# simaservo.net
KiCad netlist of a schematic drawn in EAGLE
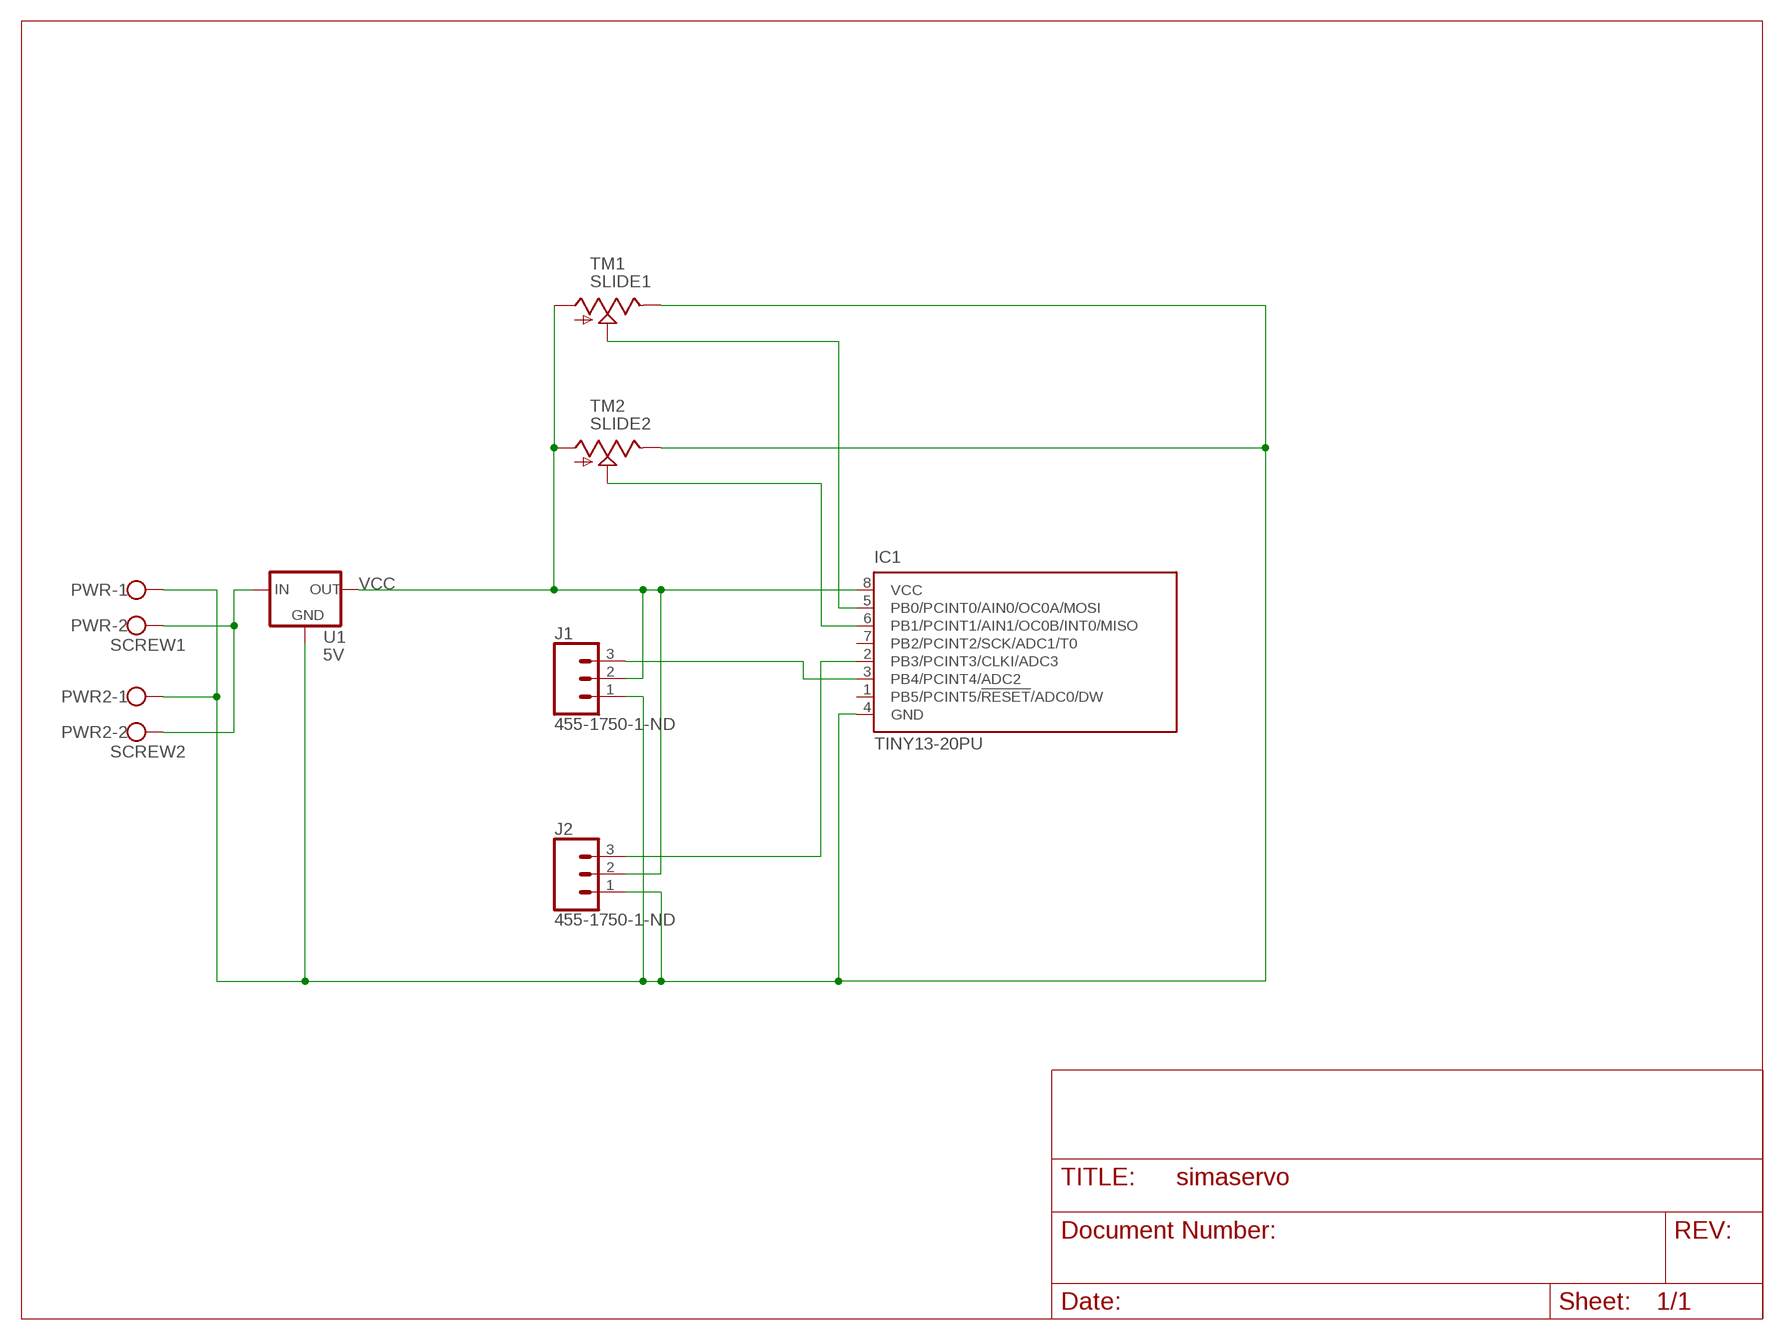
[diagram p0: schematic, sheet 1]

(export (version "E")
  (design (tool "Eeschema 10.0.6"))
  (components
    (comp (ref "IC1")
      (value "TINY13-20PU")
      (footprint "eagle-import:DIL08")
      (fields (field (name "MPN") "ATTINY13-20PU"))
      (libsource (lib "eagle-import") (part "TINY13PU-20"))
    )
    (comp (ref "J1")
      (value "455-1750-1-ND")
      (footprint "eagle-import:1X03")
      (libsource (lib "eagle-import") (part "CONN_03"))
    )
    (comp (ref "J2")
      (value "455-1750-1-ND")
      (footprint "eagle-import:1X03")
      (libsource (lib "eagle-import") (part "CONN_03"))
    )
    (comp (ref "PWR")
      (value "SCREW1")
      (footprint "eagle-import:W237-102")
      (fields (field (name "MPN") "237-102"))
      (libsource (lib "eagle-import") (part "W237-102"))
    )
    (comp (ref "PWR2")
      (value "SCREW2")
      (footprint "eagle-import:W237-102")
      (fields (field (name "MPN") "237-102"))
      (libsource (lib "eagle-import") (part "W237-102"))
    )
    (comp (ref "TM1")
      (value "SLIDE1")
      (footprint "eagle-import:SLIDEPOT-60")
      (libsource (lib "eagle-import") (part "TRIMSLIDE60"))
    )
    (comp (ref "TM2")
      (value "SLIDE2")
      (footprint "eagle-import:SLIDEPOT-60")
      (libsource (lib "eagle-import") (part "TRIMSLIDE60"))
    )
    (comp (ref "U1")
      (value "5V")
      (footprint "eagle-import:TO220-IGO")
      (libsource (lib "eagle-import") (part "V_REG_78XXSINK"))
    )
  )
  (nets
    (net (code "1") (name "/VCC") (class "Default")
      (node (ref "IC1") (pin "8") (pinfunction "VCC_8") (pintype "power_in"))
      (node (ref "J1") (pin "2") (pinfunction "2_2") (pintype "passive"))
      (node (ref "J2") (pin "2") (pinfunction "2_2") (pintype "passive"))
      (node (ref "TM1") (pin "A") (pinfunction "A_A") (pintype "passive"))
      (node (ref "TM2") (pin "A") (pinfunction "A_A") (pintype "passive"))
      (node (ref "U1") (pin "OUT") (pinfunction "OUT_OUT") (pintype "passive"))
    )
    (net (code "2") (name "Net-(IC1-GND)") (class "Default")
      (node (ref "IC1") (pin "4") (pinfunction "GND_4") (pintype "power_in"))
      (node (ref "J1") (pin "1") (pinfunction "1_1") (pintype "passive"))
      (node (ref "J2") (pin "1") (pinfunction "1_1") (pintype "passive"))
      (node (ref "PWR") (pin "1") (pinfunction "KL_1") (pintype "passive"))
      (node (ref "PWR2") (pin "1") (pinfunction "KL_1") (pintype "passive"))
      (node (ref "TM1") (pin "B") (pinfunction "B_B") (pintype "passive"))
      (node (ref "TM2") (pin "B") (pinfunction "B_B") (pintype "passive"))
      (node (ref "U1") (pin "GND") (pinfunction "GND_GND") (pintype "input"))
    )
    (net (code "3") (name "Net-(IC1-PB0{slash}PCINT0{slash}AIN0{slash}OC0A{slash}MOSI)") (class "Default")
      (node (ref "IC1") (pin "5") (pinfunction "PB0/PCINT0/AIN0/OC0A/MOSI_5") (pintype "bidirectional"))
      (node (ref "TM1") (pin "WIPER") (pinfunction "WIPER_WIPER") (pintype "passive"))
    )
    (net (code "4") (name "Net-(IC1-PB1{slash}PCINT1{slash}AIN1{slash}OC0B{slash}INT0{slash}MISO)") (class "Default")
      (node (ref "IC1") (pin "6") (pinfunction "PB1/PCINT1/AIN1/OC0B/INT0/MISO_6") (pintype "bidirectional"))
      (node (ref "TM2") (pin "WIPER") (pinfunction "WIPER_WIPER") (pintype "passive"))
    )
    (net (code "5") (name "Net-(IC1-PB3{slash}PCINT3{slash}CLKI{slash}ADC3)") (class "Default")
      (node (ref "IC1") (pin "2") (pinfunction "PB3/PCINT3/CLKI/ADC3_2") (pintype "bidirectional"))
      (node (ref "J2") (pin "3") (pinfunction "3_3") (pintype "passive"))
    )
    (net (code "6") (name "Net-(IC1-PB4{slash}PCINT4{slash}ADC2)") (class "Default")
      (node (ref "IC1") (pin "3") (pinfunction "PB4/PCINT4/ADC2_3") (pintype "bidirectional"))
      (node (ref "J1") (pin "3") (pinfunction "3_3") (pintype "passive"))
    )
    (net (code "7") (name "Net-(PWR2B-KL)") (class "Default")
      (node (ref "PWR") (pin "2") (pinfunction "KL_2") (pintype "passive"))
      (node (ref "PWR2") (pin "2") (pinfunction "KL_2") (pintype "passive"))
      (node (ref "U1") (pin "IN") (pinfunction "IN_IN") (pintype "input"))
    )
    (net (code "8") (name "unconnected-(IC1-PB2{slash}PCINT2{slash}SCK{slash}ADC1{slash}T0-Pad7)") (class "Default")
      (node (ref "IC1") (pin "7") (pinfunction "PB2/PCINT2/SCK/ADC1/T0_7") (pintype "bidirectional"))
    )
    (net (code "9") (name "unconnected-(IC1-PB5{slash}PCINT5{slash}~{RESET}{slash}ADC0{slash}DW-Pad1)") (class "Default")
      (node (ref "IC1") (pin "1") (pinfunction "PB5/PCINT5/~{RESET}/ADC0/DW_1") (pintype "bidirectional"))
    )
  )
)
